# 39-996_-_SM_Clock-Timer.net
KiCad netlist of a schematic drawn in Altium Designer
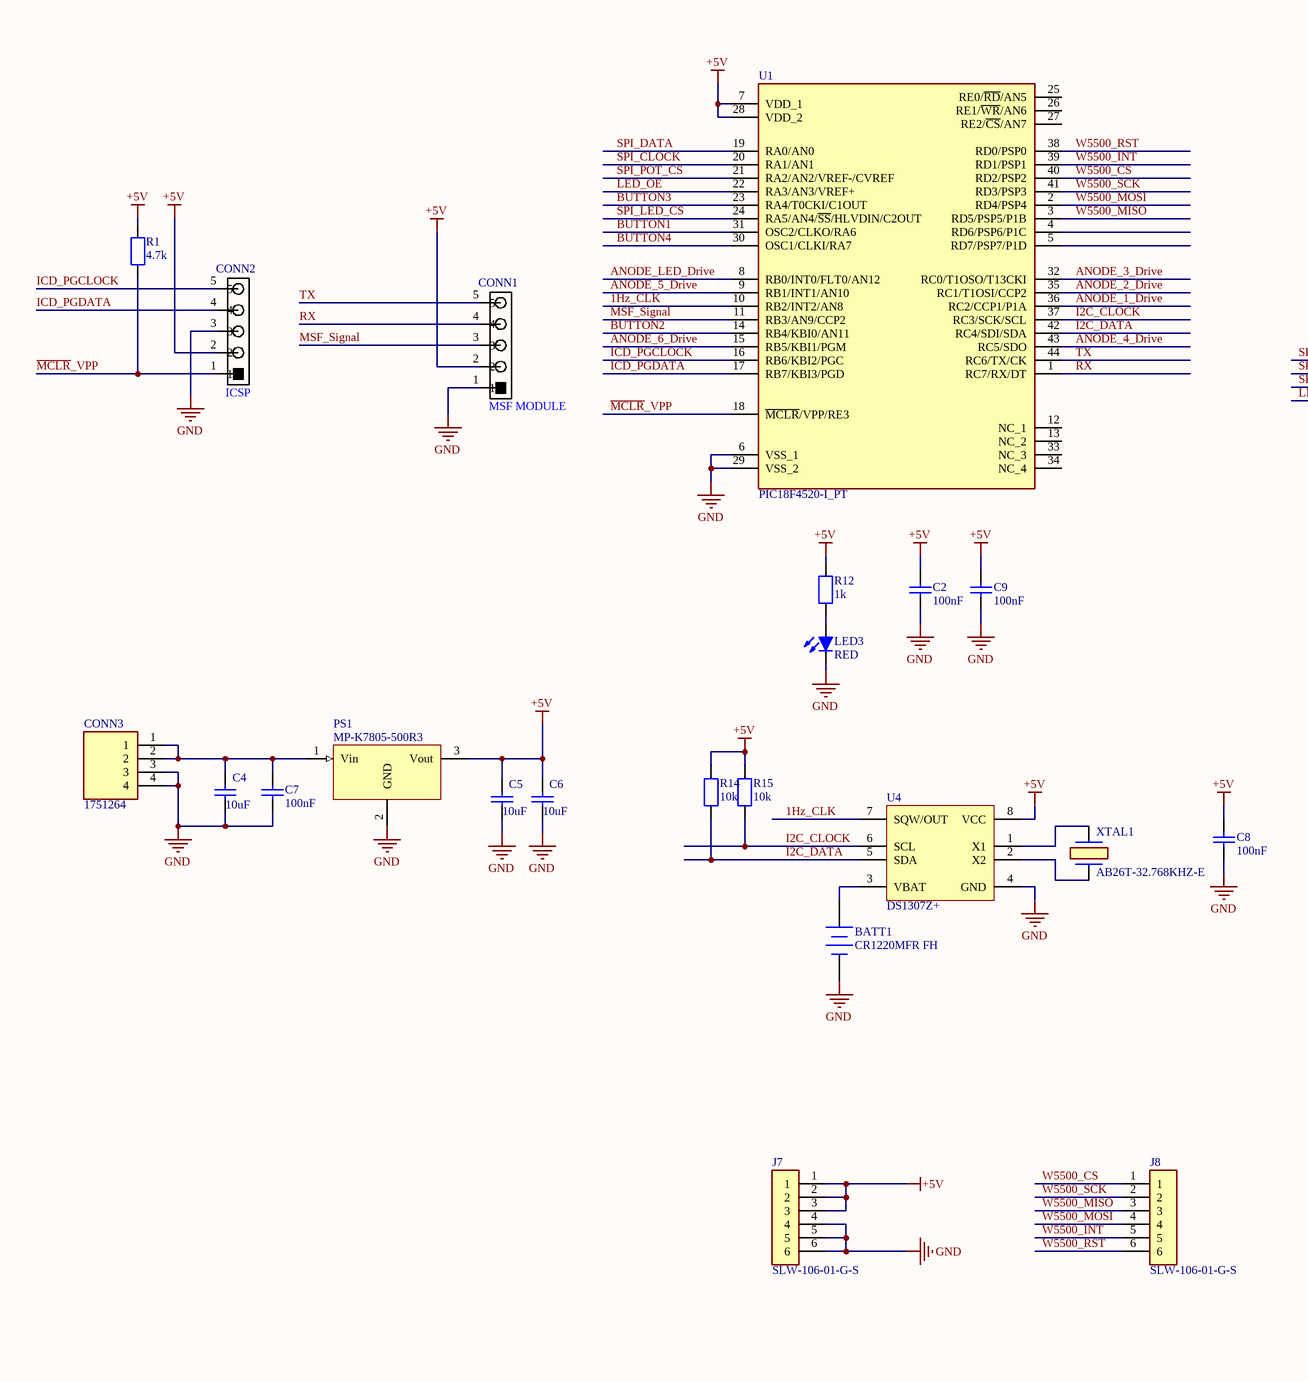
[diagram p0: 39-996 - SM Clock-Timer.SchDoc, left]
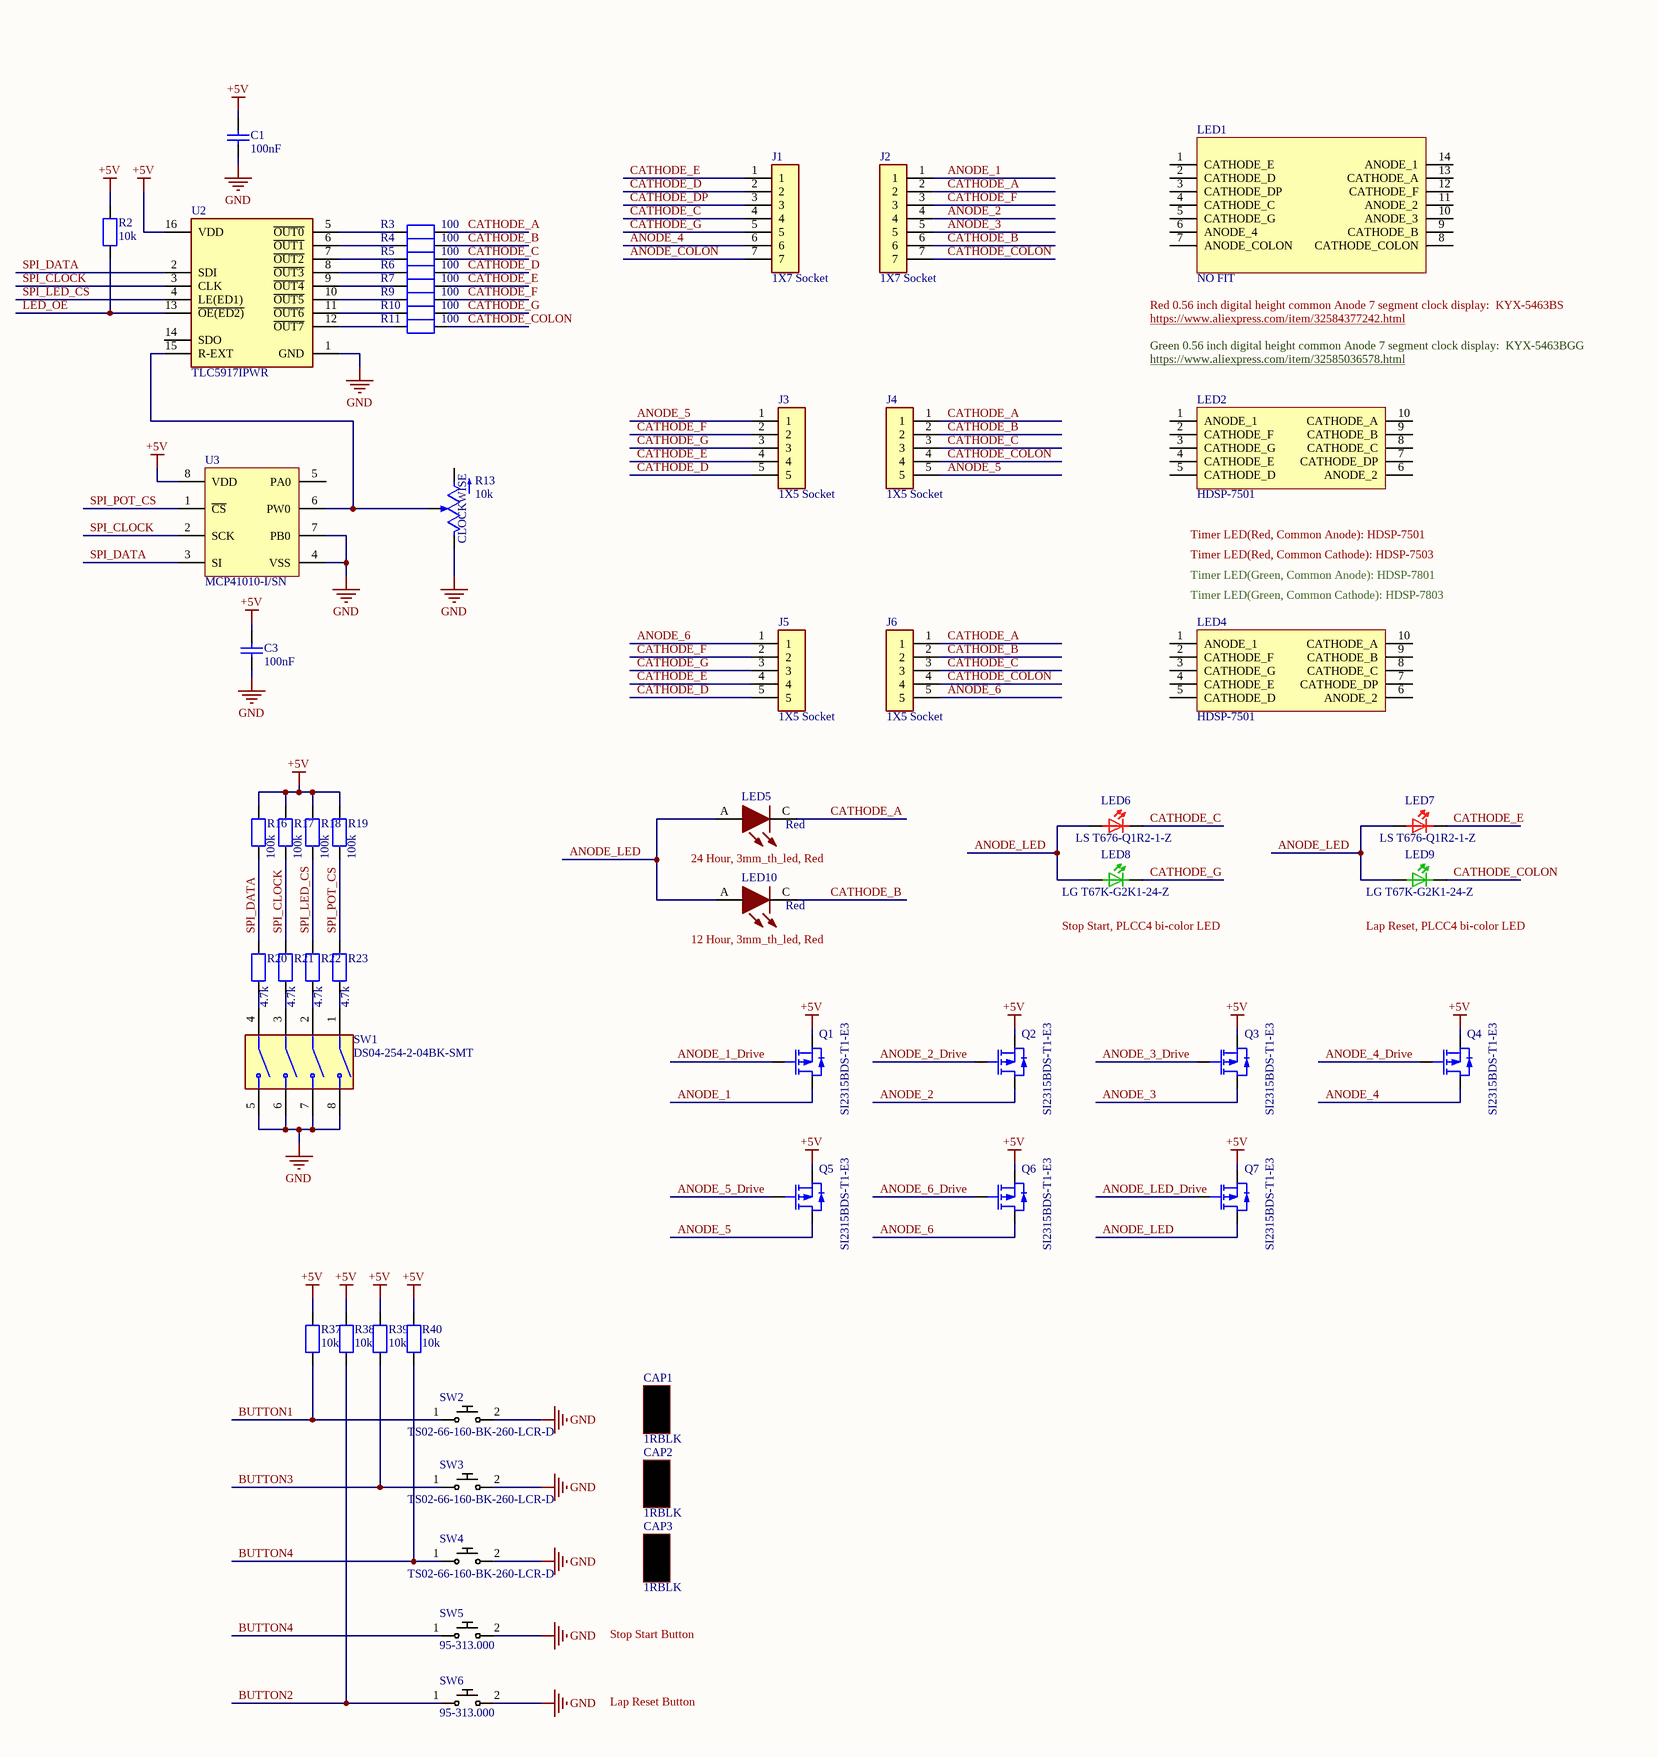
[diagram p1: 39-996 - SM Clock-Timer.SchDoc, right]

(export (version "E")
  (design (tool "Eeschema 10.0.6"))
  (components
    (comp (ref "BATT1")
      (value "CR1220MFR FH")
      (footprint "CR1220MFRFH")
      (description "Coin Cell Battery 3V2-PINHORZ40mAh")
      (fields (field (name "MANUFACTURER") "Renata"))
      (libsource (lib "SM Desk Clock-Timer") (part "CR1220MFR FH"))
    )
    (comp (ref "C1")
      (value "100nF")
      (footprint "C0603")
      (description "100nF ± 10% 50V")
      (fields (field (name "MANUFACTURER") "Yageo"))
      (libsource (lib "Cue Light Output PCB - RJ45") (part "100nF ± 10% 50V"))
    )
    (comp (ref "C2")
      (value "100nF")
      (footprint "C0603")
      (description "100nF ± 10% 50V")
      (fields (field (name "MANUFACTURER") "Yageo"))
      (libsource (lib "Cue Light Output PCB - RJ45") (part "100nF ± 10% 50V"))
    )
    (comp (ref "C3")
      (value "100nF")
      (footprint "C0603")
      (description "100nF ± 10% 50V")
      (fields (field (name "MANUFACTURER") "Yageo"))
      (libsource (lib "Cue Light Output PCB - RJ45") (part "100nF ± 10% 50V"))
    )
    (comp (ref "C4")
      (value "10uF")
      (footprint "C1206")
      (description "10uF ± 10% 50V")
      (fields (field (name "MANUFACTURER") "Yageo"))
      (libsource (lib "Cue Light Output PCB - RJ45") (part "10uF ± 10% 50V"))
    )
    (comp (ref "C5")
      (value "10uF")
      (footprint "C1206")
      (description "10uF ± 10% 50V")
      (fields (field (name "MANUFACTURER") "Yageo"))
      (libsource (lib "Cue Light Output PCB - RJ45") (part "10uF ± 10% 50V"))
    )
    (comp (ref "C6")
      (value "10uF")
      (footprint "C1206")
      (description "10uF ± 10% 50V")
      (fields (field (name "MANUFACTURER") "Yageo"))
      (libsource (lib "Cue Light Output PCB - RJ45") (part "10uF ± 10% 50V"))
    )
    (comp (ref "C7")
      (value "100nF")
      (footprint "C0603")
      (description "100nF ± 10% 50V")
      (fields (field (name "MANUFACTURER") "Yageo"))
      (libsource (lib "Cue Light Output PCB - RJ45") (part "100nF ± 10% 50V"))
    )
    (comp (ref "C8")
      (value "100nF")
      (footprint "C0603")
      (description "100nF ± 10% 50V")
      (fields (field (name "MANUFACTURER") "Yageo"))
      (libsource (lib "Cue Light Output PCB - RJ45") (part "100nF ± 10% 50V"))
    )
    (comp (ref "C9")
      (value "100nF")
      (footprint "C0603")
      (description "100nF ± 10% 50V")
      (fields (field (name "MANUFACTURER") "Yageo"))
      (libsource (lib "Cue Light Output PCB - RJ45") (part "100nF ± 10% 50V"))
    )
    (comp (ref "CAP1")
      (value "1RBLK")
      (footprint "1RBLK")
      (description "Switch Bezels / Switch Caps 9 X 5MM RND CAP BLK")
      (fields (field (name "MANUFACTURER") "E-Switch"))
      (libsource (lib "SM Desk Clock-Timer") (part "1RBLK"))
    )
    (comp (ref "CAP2")
      (value "1RBLK")
      (footprint "1RBLK")
      (description "Switch Bezels / Switch Caps 9 X 5MM RND CAP BLK")
      (fields (field (name "MANUFACTURER") "E-Switch"))
      (libsource (lib "SM Desk Clock-Timer") (part "1RBLK"))
    )
    (comp (ref "CAP3")
      (value "1RBLK")
      (footprint "1RBLK")
      (description "Switch Bezels / Switch Caps 9 X 5MM RND CAP BLK")
      (fields (field (name "MANUFACTURER") "E-Switch"))
      (libsource (lib "SM Desk Clock-Timer") (part "1RBLK"))
    )
    (comp (ref "CONN1")
      (value "NO FIT")
      (footprint "ICSP")
      (description "ICSP Header - 5 Pin, 2.54mm Pitch")
      (libsource (lib "GDS_CONN") (part "ICSP"))
    )
    (comp (ref "CONN2")
      (value "NO FIT")
      (footprint "ICSP")
      (description "ICSP Header - 5 Pin, 2.54mm Pitch")
      (libsource (lib "GDS_CONN") (part "ICSP"))
    )
    (comp (ref "CONN3")
      (value "1751264")
      (footprint "1751264")
      (description "Fixed Terminal Blocks 4P 3.5mm 90DEG")
      (fields (field (name "MANUFACTURER") "Phoenix Contact"))
      (libsource (lib "1751264") (part "1751264"))
    )
    (comp (ref "J1")
      (value "1X7 Socket")
      (footprint "D019970742")
      (description "IC & Component Sockets 7 WAY SIL VERT SKT")
      (fields (field (name "MANUFACTURER") "Harwin") (field (name "MANUFACTURER PART NUMBER") "D01-9970742"))
      (libsource (lib "SM Desk Clock-Timer") (part "D01-9970742"))
    )
    (comp (ref "J2")
      (value "1X7 Socket")
      (footprint "D019970742")
      (description "IC & Component Sockets 7 WAY SIL VERT SKT")
      (fields (field (name "MANUFACTURER") "Harwin") (field (name "MANUFACTURER PART NUMBER") "D01-9970742"))
      (libsource (lib "") (part "D01-9970742_1"))
    )
    (comp (ref "J3")
      (value "1X5 Socket")
      (footprint "D01-9970542")
      (description "IC & Component Sockets 5 WAY SIL VERT SKT")
      (fields (field (name "MANUFACTURER") "Harwin") (field (name "MANUFACTURER PART NUMBER") "D01-9970542"))
      (libsource (lib "") (part "D01-9970542_1"))
    )
    (comp (ref "J4")
      (value "1X5 Socket")
      (footprint "D01-9970542")
      (description "IC & Component Sockets 5 WAY SIL VERT SKT")
      (fields (field (name "MANUFACTURER") "Harwin") (field (name "MANUFACTURER PART NUMBER") "D01-9970542"))
      (libsource (lib "SM Desk Clock-Timer") (part "D01-9970542"))
    )
    (comp (ref "J5")
      (value "1X5 Socket")
      (footprint "D01-9970542")
      (description "IC & Component Sockets 5 WAY SIL VERT SKT")
      (fields (field (name "MANUFACTURER") "Harwin") (field (name "MANUFACTURER PART NUMBER") "D01-9970542"))
      (libsource (lib "") (part "D01-9970542_1"))
    )
    (comp (ref "J6")
      (value "1X5 Socket")
      (footprint "D01-9970542")
      (description "IC & Component Sockets 5 WAY SIL VERT SKT")
      (fields (field (name "MANUFACTURER") "Harwin") (field (name "MANUFACTURER PART NUMBER") "D01-9970542"))
      (libsource (lib "SM Desk Clock-Timer") (part "D01-9970542"))
    )
    (comp (ref "J7")
      (value "SLW-106-01-G-S")
      (footprint "SLW-106-01-G-S")
      (description "Headers & Wire Housings .100\" Tiger Buy Low Profile Socket Strip")
      (fields (field (name "MANUFACTURER") "Samtec"))
      (libsource (lib "SM Desk Clock-Timer") (part "SLW-106-01-G-S"))
    )
    (comp (ref "J8")
      (value "SLW-106-01-G-S")
      (footprint "SLW-106-01-G-S")
      (description "Headers & Wire Housings .100\" Tiger Buy Low Profile Socket Strip")
      (fields (field (name "MANUFACTURER") "Samtec"))
      (libsource (lib "") (part "SLW-106-01-G-S_1"))
    )
    (comp (ref "LED1")
      (value "NO FIT")
      (footprint "Common Cathode 7 Segment Clock Display")
      (description "0.56 inch digit height common Anode 7 segment clock display")
      (libsource (lib "SM Desk Clock-Timer") (part "Common Anode 7 Segment Clock Display"))
    )
    (comp (ref "LED2")
      (value "HDSP-7501")
      (footprint "HDSP7501")
      (description "7 SEG NUMERIC DISPLAY, HIGH EFFICIENCY RED, 7.6 mm")
      (fields (field (name "MANUFACTURER") "Avago Technologies"))
      (libsource (lib "SM Desk Clock-Timer") (part "HDSP-7501"))
    )
    (comp (ref "LED3")
      (value "RED")
      (footprint "LED_PLCC2")
      (description "Standard LEDs - SMD Super Red, 645nm 180mcd, 20mA")
      (fields
        (field (name "MANUFACTURER") "ams OSRAM")
        (field (name "MANUFACTURER PART NUMBER") "LS T676-Q1R2-1-Z")
      )
      (libsource (lib "Cue Light Output PCB - RJ45") (part "LS T676-Q1R2-1-Z"))
    )
    (comp (ref "LED4")
      (value "HDSP-7501")
      (footprint "HDSP7501")
      (description "7 SEG NUMERIC DISPLAY, HIGH EFFICIENCY RED, 7.6 mm")
      (fields (field (name "MANUFACTURER") "Avago Technologies"))
      (libsource (lib "SM Desk Clock-Timer") (part "HDSP-7501"))
    )
    (comp (ref "LED5")
      (value "Red")
      (footprint "LED_3mm")
      (description "Standard LEDs - Through Hole RED DIFFUSED")
      (fields (field (name "MANUFACTURER") "Kingbright") (field (name "MANUFACTURER PART NUMBER") "WP132XID"))
      (libsource (lib "SM Desk Clock-Timer") (part "WP132XID"))
    )
    (comp (ref "LED6")
      (value "LS T676-Q1R2-1-Z")
      (footprint "PLCC-2")
      (description "Standard LEDs - SMD Super Red, 645nm 180mcd, 20mA")
      (fields (field (name "MANUFACTURER") "ams OSRAM"))
      (libsource (lib "47-538 - Desk Power CTRL Button") (part "LS T676-Q1R2-1-Z"))
    )
    (comp (ref "LED7")
      (value "LS T676-Q1R2-1-Z")
      (footprint "PLCC-2")
      (description "Standard LEDs - SMD Super Red, 645nm 180mcd, 20mA")
      (fields (field (name "MANUFACTURER") "ams OSRAM"))
      (libsource (lib "47-538 - Desk Power CTRL Button") (part "LS T676-Q1R2-1-Z"))
    )
    (comp (ref "LED8")
      (value "LG T67K-G2K1-24-Z")
      (footprint "PLCC-2")
      (description "Standard LEDs - SMD Green 570nm, 20mA")
      (fields (field (name "MANUFACTURER") "ams OSRAM"))
      (libsource (lib "47-538 - Desk Power CTRL Button") (part "LG T67K-G2K1-24-Z"))
    )
    (comp (ref "LED9")
      (value "LG T67K-G2K1-24-Z")
      (footprint "PLCC-2")
      (description "Standard LEDs - SMD Green 570nm, 20mA")
      (fields (field (name "MANUFACTURER") "ams OSRAM"))
      (libsource (lib "47-538 - Desk Power CTRL Button") (part "LG T67K-G2K1-24-Z"))
    )
    (comp (ref "LED10")
      (value "Red")
      (footprint "LED_3mm")
      (description "Standard LEDs - Through Hole RED DIFFUSED")
      (fields (field (name "MANUFACTURER") "Kingbright") (field (name "MANUFACTURER PART NUMBER") "WP132XID"))
      (libsource (lib "SM Desk Clock-Timer") (part "WP132XID"))
    )
    (comp (ref "PS1")
      (value "MP-K7805-500R3")
      (footprint "CONV_K7805-500R3")
      (fields (field (name "MANUFACTURER") "MULTICOMP PRO"))
      (libsource (lib "SM Desk Clock-Timer") (part "MP-K7805-500R3"))
    )
    (comp (ref "Q1")
      (value "SI2315BDS-T1-E3")
      (footprint "SOT23-3")
      (description "MOSFET 1.8V 3.2A 1.25W")
      (fields (field (name "MANUFACTURER") "Vishay Semiconductors"))
      (libsource (lib "SM Desk Clock-Timer") (part "SI2315BDS-T1-E3"))
    )
    (comp (ref "Q2")
      (value "SI2315BDS-T1-E3")
      (footprint "SOT23-3")
      (description "MOSFET 1.8V 3.2A 1.25W")
      (fields (field (name "MANUFACTURER") "Vishay Semiconductors"))
      (libsource (lib "SM Desk Clock-Timer") (part "SI2315BDS-T1-E3"))
    )
    (comp (ref "Q3")
      (value "SI2315BDS-T1-E3")
      (footprint "SOT23-3")
      (description "MOSFET 1.8V 3.2A 1.25W")
      (fields (field (name "MANUFACTURER") "Vishay Semiconductors"))
      (libsource (lib "SM Desk Clock-Timer") (part "SI2315BDS-T1-E3"))
    )
    (comp (ref "Q4")
      (value "SI2315BDS-T1-E3")
      (footprint "SOT23-3")
      (description "MOSFET 1.8V 3.2A 1.25W")
      (fields (field (name "MANUFACTURER") "Vishay Semiconductors"))
      (libsource (lib "SM Desk Clock-Timer") (part "SI2315BDS-T1-E3"))
    )
    (comp (ref "Q5")
      (value "SI2315BDS-T1-E3")
      (footprint "SOT23-3")
      (description "MOSFET 1.8V 3.2A 1.25W")
      (fields (field (name "MANUFACTURER") "Vishay Semiconductors"))
      (libsource (lib "SM Desk Clock-Timer") (part "SI2315BDS-T1-E3"))
    )
    (comp (ref "Q6")
      (value "SI2315BDS-T1-E3")
      (footprint "SOT23-3")
      (description "MOSFET 1.8V 3.2A 1.25W")
      (fields (field (name "MANUFACTURER") "Vishay Semiconductors"))
      (libsource (lib "SM Desk Clock-Timer") (part "SI2315BDS-T1-E3"))
    )
    (comp (ref "Q7")
      (value "SI2315BDS-T1-E3")
      (footprint "SOT23-3")
      (description "MOSFET 1.8V 3.2A 1.25W")
      (fields (field (name "MANUFACTURER") "Vishay Semiconductors"))
      (libsource (lib "SM Desk Clock-Timer") (part "SI2315BDS-T1-E3"))
    )
    (comp (ref "R1")
      (value "4.7k")
      (footprint "R0603")
      (description "4.7 kOhms ±1% 0.1W")
      (fields
        (field (name "MANUFACTURER") "Yageo")
        (field (name "MANUFACTURER PART NUMBER") "RC0603FR-074K7L")
      )
      (libsource (lib "32-503 - DriveHUB - 1Ch 10A Variable CV") (part "4.7 kOhms ±1% 0.1W"))
    )
    (comp (ref "R2")
      (value "10k")
      (footprint "R0603")
      (description "10 kOhms ±1% 0.1W")
      (fields
        (field (name "MANUFACTURER") "Yageo")
        (field (name "MANUFACTURER PART NUMBER") "RC0603FR-0710KL")
      )
      (libsource (lib "SM Desk Clock-Timer") (part "10 kOhms ±1% 0.1W"))
    )
    (comp (ref "R3")
      (value "100")
      (footprint "R0603")
      (description "100 Ohms ±1% 0.1W")
      (fields
        (field (name "MANUFACTURER") "Yageo")
        (field (name "MANUFACTURER PART NUMBER") "RC0603FR-07100RL")
      )
      (libsource (lib "SM Desk Clock-Timer") (part "100 Ohms ±1% 0.1W"))
    )
    (comp (ref "R4")
      (value "100")
      (footprint "R0603")
      (description "100 Ohms ±1% 0.1W")
      (fields
        (field (name "MANUFACTURER") "Yageo")
        (field (name "MANUFACTURER PART NUMBER") "RC0603FR-07100RL")
      )
      (libsource (lib "SM Desk Clock-Timer") (part "100 Ohms ±1% 0.1W"))
    )
    (comp (ref "R5")
      (value "100")
      (footprint "R0603")
      (description "100 Ohms ±1% 0.1W")
      (fields
        (field (name "MANUFACTURER") "Yageo")
        (field (name "MANUFACTURER PART NUMBER") "RC0603FR-07100RL")
      )
      (libsource (lib "SM Desk Clock-Timer") (part "100 Ohms ±1% 0.1W"))
    )
    (comp (ref "R6")
      (value "100")
      (footprint "R0603")
      (description "100 Ohms ±1% 0.1W")
      (fields
        (field (name "MANUFACTURER") "Yageo")
        (field (name "MANUFACTURER PART NUMBER") "RC0603FR-07100RL")
      )
      (libsource (lib "SM Desk Clock-Timer") (part "100 Ohms ±1% 0.1W"))
    )
    (comp (ref "R7")
      (value "100")
      (footprint "R0603")
      (description "100 Ohms ±1% 0.1W")
      (fields
        (field (name "MANUFACTURER") "Yageo")
        (field (name "MANUFACTURER PART NUMBER") "RC0603FR-07100RL")
      )
      (libsource (lib "SM Desk Clock-Timer") (part "100 Ohms ±1% 0.1W"))
    )
    (comp (ref "R9")
      (value "100")
      (footprint "R0603")
      (description "100 Ohms ±1% 0.1W")
      (fields
        (field (name "MANUFACTURER") "Yageo")
        (field (name "MANUFACTURER PART NUMBER") "RC0603FR-07100RL")
      )
      (libsource (lib "SM Desk Clock-Timer") (part "100 Ohms ±1% 0.1W"))
    )
    (comp (ref "R10")
      (value "100")
      (footprint "R0603")
      (description "100 Ohms ±1% 0.1W")
      (fields
        (field (name "MANUFACTURER") "Yageo")
        (field (name "MANUFACTURER PART NUMBER") "RC0603FR-07100RL")
      )
      (libsource (lib "SM Desk Clock-Timer") (part "100 Ohms ±1% 0.1W"))
    )
    (comp (ref "R11")
      (value "100")
      (footprint "R0603")
      (description "100 Ohms ±1% 0.1W")
      (fields
        (field (name "MANUFACTURER") "Yageo")
        (field (name "MANUFACTURER PART NUMBER") "RC0603FR-07100RL")
      )
      (libsource (lib "SM Desk Clock-Timer") (part "100 Ohms ±1% 0.1W"))
    )
    (comp (ref "R12")
      (value "1k")
      (footprint "R0603")
      (description "1 kOhms ±1% 0.1W")
      (fields
        (field (name "MANUFACTURER") "Yageo")
        (field (name "MANUFACTURER PART NUMBER") "RC0603FR-071KL")
      )
      (libsource (lib "SM Desk Clock-Timer") (part "1 kOhms ±1% 0.1W"))
    )
    (comp (ref "R13")
      (value "10k")
      (footprint "TRIM_3386F-1-103LF")
      (description "Trimmer Resistors - Through Hole 3/8\" 10Kohms 10% 0.5Watts Square")
      (fields
        (field (name "MANUFACTURER") "Bourns")
        (field (name "MANUFACTURER PART NUMBER") "3386F-1-103LF")
      )
      (libsource (lib "SM Desk Clock-Timer") (part "3386F-1-103LF"))
    )
    (comp (ref "R14")
      (value "10k")
      (footprint "R0603")
      (description "10 kOhms ±1% 0.1W")
      (fields
        (field (name "MANUFACTURER") "Yageo")
        (field (name "MANUFACTURER PART NUMBER") "RC0603FR-0710KL")
      )
      (libsource (lib "SM Desk Clock-Timer") (part "10 kOhms ±1% 0.1W"))
    )
    (comp (ref "R15")
      (value "10k")
      (footprint "R0603")
      (description "10 kOhms ±1% 0.1W")
      (fields
        (field (name "MANUFACTURER") "Yageo")
        (field (name "MANUFACTURER PART NUMBER") "RC0603FR-0710KL")
      )
      (libsource (lib "SM Desk Clock-Timer") (part "10 kOhms ±1% 0.1W"))
    )
    (comp (ref "R16")
      (value "100k")
      (footprint "R0603")
      (description "100 kOhms ±1% 0.1W")
      (fields
        (field (name "MANUFACTURER") "Yageo")
        (field (name "MANUFACTURER PART NUMBER") "RC0603FR-07100KL")
      )
      (libsource (lib "SM Desk Clock-Timer") (part "100 kOhms ±1% 0.1W"))
    )
    (comp (ref "R17")
      (value "100k")
      (footprint "R0603")
      (description "100 kOhms ±1% 0.1W")
      (fields
        (field (name "MANUFACTURER") "Yageo")
        (field (name "MANUFACTURER PART NUMBER") "RC0603FR-07100KL")
      )
      (libsource (lib "SM Desk Clock-Timer") (part "100 kOhms ±1% 0.1W"))
    )
    (comp (ref "R18")
      (value "100k")
      (footprint "R0603")
      (description "100 kOhms ±1% 0.1W")
      (fields
        (field (name "MANUFACTURER") "Yageo")
        (field (name "MANUFACTURER PART NUMBER") "RC0603FR-07100KL")
      )
      (libsource (lib "SM Desk Clock-Timer") (part "100 kOhms ±1% 0.1W"))
    )
    (comp (ref "R19")
      (value "100k")
      (footprint "R0603")
      (description "100 kOhms ±1% 0.1W")
      (fields
        (field (name "MANUFACTURER") "Yageo")
        (field (name "MANUFACTURER PART NUMBER") "RC0603FR-07100KL")
      )
      (libsource (lib "SM Desk Clock-Timer") (part "100 kOhms ±1% 0.1W"))
    )
    (comp (ref "R20")
      (value "4.7k")
      (footprint "R0603")
      (description "4.7 kOhms ±1% 0.1W")
      (fields
        (field (name "MANUFACTURER") "Yageo")
        (field (name "MANUFACTURER PART NUMBER") "RC0603FR-074K7L")
      )
      (libsource (lib "32-503 - DriveHUB - 1Ch 10A Variable CV") (part "4.7 kOhms ±1% 0.1W"))
    )
    (comp (ref "R21")
      (value "4.7k")
      (footprint "R0603")
      (description "4.7 kOhms ±1% 0.1W")
      (fields
        (field (name "MANUFACTURER") "Yageo")
        (field (name "MANUFACTURER PART NUMBER") "RC0603FR-074K7L")
      )
      (libsource (lib "32-503 - DriveHUB - 1Ch 10A Variable CV") (part "4.7 kOhms ±1% 0.1W"))
    )
    (comp (ref "R22")
      (value "4.7k")
      (footprint "R0603")
      (description "4.7 kOhms ±1% 0.1W")
      (fields
        (field (name "MANUFACTURER") "Yageo")
        (field (name "MANUFACTURER PART NUMBER") "RC0603FR-074K7L")
      )
      (libsource (lib "32-503 - DriveHUB - 1Ch 10A Variable CV") (part "4.7 kOhms ±1% 0.1W"))
    )
    (comp (ref "R23")
      (value "4.7k")
      (footprint "R0603")
      (description "4.7 kOhms ±1% 0.1W")
      (fields
        (field (name "MANUFACTURER") "Yageo")
        (field (name "MANUFACTURER PART NUMBER") "RC0603FR-074K7L")
      )
      (libsource (lib "32-503 - DriveHUB - 1Ch 10A Variable CV") (part "4.7 kOhms ±1% 0.1W"))
    )
    (comp (ref "R37")
      (value "10k")
      (footprint "R0603")
      (description "10 kOhms ±1% 0.1W")
      (fields
        (field (name "MANUFACTURER") "Yageo")
        (field (name "MANUFACTURER PART NUMBER") "RC0603FR-0710KL")
      )
      (libsource (lib "SM Desk Clock-Timer") (part "10 kOhms ±1% 0.1W"))
    )
    (comp (ref "R38")
      (value "10k")
      (footprint "R0603")
      (description "10 kOhms ±1% 0.1W")
      (fields
        (field (name "MANUFACTURER") "Yageo")
        (field (name "MANUFACTURER PART NUMBER") "RC0603FR-0710KL")
      )
      (libsource (lib "SM Desk Clock-Timer") (part "10 kOhms ±1% 0.1W"))
    )
    (comp (ref "R39")
      (value "10k")
      (footprint "R0603")
      (description "10 kOhms ±1% 0.1W")
      (fields
        (field (name "MANUFACTURER") "Yageo")
        (field (name "MANUFACTURER PART NUMBER") "RC0603FR-0710KL")
      )
      (libsource (lib "SM Desk Clock-Timer") (part "10 kOhms ±1% 0.1W"))
    )
    (comp (ref "R40")
      (value "10k")
      (footprint "R0603")
      (description "10 kOhms ±1% 0.1W")
      (fields
        (field (name "MANUFACTURER") "Yageo")
        (field (name "MANUFACTURER PART NUMBER") "RC0603FR-0710KL")
      )
      (libsource (lib "SM Desk Clock-Timer") (part "10 kOhms ±1% 0.1W"))
    )
    (comp (ref "SW1")
      (value "DS04-254-2-04BK-SMT")
      (footprint "SW_DS04-254-2-04BK-SMT")
      (description "DIP Switches/SIP Switches DIP Switch, SPST, 2.54 pitch, flat actuator, SMT, 4 position, Black")
      (fields (field (name "MANUFACTURER") "CUI Devices"))
      (libsource (lib "SM Desk Clock-Timer") (part "DS04-254-2-04BK-SMT"))
    )
    (comp (ref "SW2")
      (value "TS02-66-160-BK-260-LCR-D")
      (footprint "SW_TS02-66-160-BK-260-LCR-D")
      (description "Tactile Switches 6 x 6 mm, 16 mm Act Height, 260 gf, Black, Long Crimped, Through Hole, SPST,")
      (fields (field (name "MANUFACTURER") "CUI Devices"))
      (libsource (lib "SM Desk Clock-Timer") (part "TS02-66-160-BK-260-LCR-D"))
    )
    (comp (ref "SW3")
      (value "TS02-66-160-BK-260-LCR-D")
      (footprint "SW_TS02-66-160-BK-260-LCR-D")
      (description "Tactile Switches 6 x 6 mm, 16 mm Act Height, 260 gf, Black, Long Crimped, Through Hole, SPST,")
      (fields (field (name "MANUFACTURER") "CUI Devices"))
      (libsource (lib "SM Desk Clock-Timer") (part "TS02-66-160-BK-260-LCR-D"))
    )
    (comp (ref "SW4")
      (value "TS02-66-160-BK-260-LCR-D")
      (footprint "SW_TS02-66-160-BK-260-LCR-D")
      (description "Tactile Switches 6 x 6 mm, 16 mm Act Height, 260 gf, Black, Long Crimped, Through Hole, SPST,")
      (fields (field (name "MANUFACTURER") "CUI Devices"))
      (libsource (lib "SM Desk Clock-Timer") (part "TS02-66-160-BK-260-LCR-D"))
    )
    (comp (ref "SW5")
      (value "95-313.000")
      (footprint "PUSHBUTTON_95-313.000")
      (description "Switching element square, 12.7 x 12.7 mm")
      (fields (field (name "MANUFACTURER") "eao"))
      (libsource (lib "47-538 - Desk Power CTRL Button") (part "95-313.000"))
    )
    (comp (ref "SW6")
      (value "95-313.000")
      (footprint "PUSHBUTTON_95-313.000")
      (description "Switching element square, 12.7 x 12.7 mm")
      (fields (field (name "MANUFACTURER") "eao"))
      (libsource (lib "47-538 - Desk Power CTRL Button") (part "95-313.000"))
    )
    (comp (ref "U1")
      (value "PIC18F4520-I_PT")
      (footprint "TQFP-44")
      (description "MCU 32 KB Flash,1536 RAM, 36 I/O")
      (fields
        (field (name "MANUFACTURER") "Microchip")
        (field (name "MANUFACTURER PART NUMBER") "PIC18F4520-I/PT")
      )
      (libsource (lib "SM Desk Clock-Timer") (part "PIC18F4520-I_PT"))
    )
    (comp (ref "U2")
      (value "TLC5917IPWR")
      (footprint "SOIC-16")
      (description "LED Lighting Drivers 8B Constant-Current LED Sink")
      (fields (field (name "MANUFACTURER") "Texas Instruments"))
      (libsource (lib "SM Desk Clock-Timer") (part "TLC5917IPWR"))
    )
    (comp (ref "U3")
      (value "MCP41010-I/SN")
      (footprint "SOIC-8")
      (description "Digital Potentiometer 10K 256pos SPI SO8")
      (fields (field (name "MANUFACTURER") "Microchip"))
      (libsource (lib "SM Desk Clock-Timer") (part "MCP41010-I/SN"))
    )
    (comp (ref "U4")
      (value "DS1307Z+")
      (footprint "SOIC-8")
      (description "DS1307Z+, Real Time Clock, Alarm, Calendar, Clock, 56B RAM, I2C, 5V, 8-Pin SOIC")
      (fields (field (name "MANUFACTURER") "Analog Devices"))
      (libsource (lib "SM Desk Clock-Timer") (part "DS1307Z+"))
    )
    (comp (ref "XTAL1")
      (value "AB26T-32.768KHZ-E")
      (footprint "AB26T32768KHZE")
      (description "OSC XO 1.33GHZ 2.5V LVPECL")
      (fields (field (name "MANUFACTURER") "ABRACON"))
      (libsource (lib "SM Desk Clock-Timer") (part "AB26T-32.768KHZ-E"))
    )
  )
  (nets
    (net (code "1") (name "+5V") (class "Default")
      (node (ref "C1") (pin "2") (pinfunction "2_2") (pintype "passive"))
      (node (ref "C2") (pin "2") (pinfunction "2_2") (pintype "passive"))
      (node (ref "C3") (pin "2") (pinfunction "2_2") (pintype "passive"))
      (node (ref "C5") (pin "2") (pinfunction "2_2") (pintype "passive"))
      (node (ref "C6") (pin "2") (pinfunction "2_2") (pintype "passive"))
      (node (ref "C8") (pin "2") (pinfunction "2_2") (pintype "passive"))
      (node (ref "C9") (pin "2") (pinfunction "2_2") (pintype "passive"))
      (node (ref "CONN1") (pin "2") (pinfunction "2_2") (pintype "passive"))
      (node (ref "CONN2") (pin "2") (pinfunction "2_2") (pintype "passive"))
      (node (ref "J7") (pin "1") (pinfunction "1_1") (pintype "passive"))
      (node (ref "J7") (pin "2") (pinfunction "2_2") (pintype "passive"))
      (node (ref "J7") (pin "3") (pinfunction "3_3") (pintype "passive"))
      (node (ref "PS1") (pin "3") (pinfunction "Vout_3") (pintype "passive"))
      (node (ref "Q1") (pin "2") (pinfunction "S_2") (pintype "passive"))
      (node (ref "Q2") (pin "2") (pinfunction "S_2") (pintype "passive"))
      (node (ref "Q3") (pin "2") (pinfunction "S_2") (pintype "passive"))
      (node (ref "Q4") (pin "2") (pinfunction "S_2") (pintype "passive"))
      (node (ref "Q5") (pin "2") (pinfunction "S_2") (pintype "passive"))
      (node (ref "Q6") (pin "2") (pinfunction "S_2") (pintype "passive"))
      (node (ref "Q7") (pin "2") (pinfunction "S_2") (pintype "passive"))
      (node (ref "R1") (pin "2") (pinfunction "2_2") (pintype "passive"))
      (node (ref "R12") (pin "2") (pinfunction "2_2") (pintype "passive"))
      (node (ref "R14") (pin "2") (pinfunction "2_2") (pintype "passive"))
      (node (ref "R15") (pin "2") (pinfunction "2_2") (pintype "passive"))
      (node (ref "R16") (pin "2") (pinfunction "2_2") (pintype "passive"))
      (node (ref "R17") (pin "2") (pinfunction "2_2") (pintype "passive"))
      (node (ref "R18") (pin "2") (pinfunction "2_2") (pintype "passive"))
      (node (ref "R19") (pin "2") (pinfunction "2_2") (pintype "passive"))
      (node (ref "R2") (pin "2") (pinfunction "2_2") (pintype "passive"))
      (node (ref "R37") (pin "2") (pinfunction "2_2") (pintype "passive"))
      (node (ref "R38") (pin "2") (pinfunction "2_2") (pintype "passive"))
      (node (ref "R39") (pin "2") (pinfunction "2_2") (pintype "passive"))
      (node (ref "R40") (pin "2") (pinfunction "2_2") (pintype "passive"))
      (node (ref "U1") (pin "28") (pinfunction "VDD_2_28") (pintype "passive"))
      (node (ref "U1") (pin "7") (pinfunction "VDD_1_7") (pintype "passive"))
      (node (ref "U2") (pin "16") (pinfunction "VDD_16") (pintype "passive"))
      (node (ref "U3") (pin "8") (pinfunction "VDD_8") (pintype "passive"))
      (node (ref "U4") (pin "8") (pinfunction "VCC_8") (pintype "passive"))
    )
    (net (code "2") (name "/1Hz_CLK") (class "Default")
      (node (ref "U1") (pin "10") (pinfunction "RB2/INT2/AN8_10") (pintype "passive"))
      (node (ref "U4") (pin "7") (pinfunction "SQW/OUT_7") (pintype "passive"))
    )
    (net (code "3") (name "/ANODE_1") (class "Default")
      (node (ref "J2") (pin "1") (pinfunction "1_1") (pintype "passive"))
      (node (ref "Q1") (pin "3") (pinfunction "D_3") (pintype "passive"))
    )
    (net (code "4") (name "/ANODE_1_Drive") (class "Default")
      (node (ref "Q1") (pin "1") (pinfunction "G_1") (pintype "passive"))
      (node (ref "U1") (pin "36") (pinfunction "RC2/CCP1/P1A_36") (pintype "passive"))
    )
    (net (code "5") (name "/ANODE_2") (class "Default")
      (node (ref "J2") (pin "4") (pinfunction "4_4") (pintype "passive"))
      (node (ref "Q2") (pin "3") (pinfunction "D_3") (pintype "passive"))
    )
    (net (code "6") (name "/ANODE_2_Drive") (class "Default")
      (node (ref "Q2") (pin "1") (pinfunction "G_1") (pintype "passive"))
      (node (ref "U1") (pin "35") (pinfunction "RC1/T1OSI/CCP2_35") (pintype "passive"))
    )
    (net (code "7") (name "/ANODE_3") (class "Default")
      (node (ref "J2") (pin "5") (pinfunction "5_5") (pintype "passive"))
      (node (ref "Q3") (pin "3") (pinfunction "D_3") (pintype "passive"))
    )
    (net (code "8") (name "/ANODE_3_Drive") (class "Default")
      (node (ref "Q3") (pin "1") (pinfunction "G_1") (pintype "passive"))
      (node (ref "U1") (pin "32") (pinfunction "RC0/T1OSO/T13CKI_32") (pintype "passive"))
    )
    (net (code "9") (name "/ANODE_4") (class "Default")
      (node (ref "J1") (pin "6") (pinfunction "6_6") (pintype "passive"))
      (node (ref "Q4") (pin "3") (pinfunction "D_3") (pintype "passive"))
    )
    (net (code "10") (name "/ANODE_4_Drive") (class "Default")
      (node (ref "Q4") (pin "1") (pinfunction "G_1") (pintype "passive"))
      (node (ref "U1") (pin "43") (pinfunction "RC5/SDO_43") (pintype "passive"))
    )
    (net (code "11") (name "/ANODE_5") (class "Default")
      (node (ref "J3") (pin "1") (pinfunction "1_1") (pintype "passive"))
      (node (ref "J4") (pin "5") (pinfunction "5_5") (pintype "passive"))
      (node (ref "Q5") (pin "3") (pinfunction "D_3") (pintype "passive"))
    )
    (net (code "12") (name "/ANODE_5_Drive") (class "Default")
      (node (ref "Q5") (pin "1") (pinfunction "G_1") (pintype "passive"))
      (node (ref "U1") (pin "9") (pinfunction "RB1/INT1/AN10_9") (pintype "passive"))
    )
    (net (code "13") (name "/ANODE_6") (class "Default")
      (node (ref "J5") (pin "1") (pinfunction "1_1") (pintype "passive"))
      (node (ref "J6") (pin "5") (pinfunction "5_5") (pintype "passive"))
      (node (ref "Q6") (pin "3") (pinfunction "D_3") (pintype "passive"))
    )
    (net (code "14") (name "/ANODE_6_Drive") (class "Default")
      (node (ref "Q6") (pin "1") (pinfunction "G_1") (pintype "passive"))
      (node (ref "U1") (pin "15") (pinfunction "RB5/KBI1/PGM_15") (pintype "passive"))
    )
    (net (code "15") (name "/ANODE_COLON") (class "Default")
      (node (ref "J1") (pin "7") (pinfunction "7_7") (pintype "passive"))
    )
    (net (code "16") (name "/ANODE_LED") (class "Default")
      (node (ref "LED10") (pin "A") (pinfunction "A_A") (pintype "passive"))
      (node (ref "LED5") (pin "A") (pinfunction "A_A") (pintype "passive"))
      (node (ref "LED6") (pin "A") (pinfunction "A_A") (pintype "passive"))
      (node (ref "LED7") (pin "A") (pinfunction "A_A") (pintype "passive"))
      (node (ref "LED8") (pin "A") (pinfunction "A_A") (pintype "passive"))
      (node (ref "LED9") (pin "A") (pinfunction "A_A") (pintype "passive"))
      (node (ref "Q7") (pin "3") (pinfunction "D_3") (pintype "passive"))
    )
    (net (code "17") (name "/ANODE_LED_Drive") (class "Default")
      (node (ref "Q7") (pin "1") (pinfunction "G_1") (pintype "passive"))
      (node (ref "U1") (pin "8") (pinfunction "RB0/INT0/FLT0/AN12_8") (pintype "passive"))
    )
    (net (code "18") (name "/BUTTON1") (class "Default")
      (node (ref "R37") (pin "1") (pinfunction "1_1") (pintype "passive"))
      (node (ref "SW2") (pin "1") (pinfunction "1_1") (pintype "passive"))
      (node (ref "U1") (pin "31") (pinfunction "OSC2/CLKO/RA6_31") (pintype "passive"))
    )
    (net (code "19") (name "/BUTTON2") (class "Default")
      (node (ref "R38") (pin "1") (pinfunction "1_1") (pintype "passive"))
      (node (ref "SW6") (pin "1") (pinfunction "1_1") (pintype "passive"))
      (node (ref "U1") (pin "14") (pinfunction "RB4/KBI0/AN11_14") (pintype "passive"))
    )
    (net (code "20") (name "/BUTTON3") (class "Default")
      (node (ref "R39") (pin "1") (pinfunction "1_1") (pintype "passive"))
      (node (ref "SW3") (pin "1") (pinfunction "1_1") (pintype "passive"))
      (node (ref "U1") (pin "23") (pinfunction "RA4/T0CKI/C1OUT_23") (pintype "passive"))
    )
    (net (code "21") (name "/BUTTON4") (class "Default")
      (node (ref "R40") (pin "1") (pinfunction "1_1") (pintype "passive"))
      (node (ref "SW4") (pin "1") (pinfunction "1_1") (pintype "passive"))
      (node (ref "SW5") (pin "1") (pinfunction "1_1") (pintype "passive"))
      (node (ref "U1") (pin "30") (pinfunction "OSC1/CLKI/RA7_30") (pintype "passive"))
    )
    (net (code "22") (name "/CATHODE_A") (class "Default")
      (node (ref "J2") (pin "2") (pinfunction "2_2") (pintype "passive"))
      (node (ref "J4") (pin "1") (pinfunction "1_1") (pintype "passive"))
      (node (ref "J6") (pin "1") (pinfunction "1_1") (pintype "passive"))
      (node (ref "LED5") (pin "C") (pinfunction "C_C") (pintype "passive"))
      (node (ref "R3") (pin "2") (pinfunction "2_2") (pintype "passive"))
    )
    (net (code "23") (name "/CATHODE_B") (class "Default")
      (node (ref "J2") (pin "6") (pinfunction "6_6") (pintype "passive"))
      (node (ref "J4") (pin "2") (pinfunction "2_2") (pintype "passive"))
      (node (ref "J6") (pin "2") (pinfunction "2_2") (pintype "passive"))
      (node (ref "LED10") (pin "C") (pinfunction "C_C") (pintype "passive"))
      (node (ref "R4") (pin "2") (pinfunction "2_2") (pintype "passive"))
    )
    (net (code "24") (name "/CATHODE_C") (class "Default")
      (node (ref "J1") (pin "4") (pinfunction "4_4") (pintype "passive"))
      (node (ref "J4") (pin "3") (pinfunction "3_3") (pintype "passive"))
      (node (ref "J6") (pin "3") (pinfunction "3_3") (pintype "passive"))
      (node (ref "LED6") (pin "C") (pinfunction "C_C") (pintype "passive"))
      (node (ref "R5") (pin "2") (pinfunction "2_2") (pintype "passive"))
    )
    (net (code "25") (name "/CATHODE_COLON") (class "Default")
      (node (ref "J2") (pin "7") (pinfunction "7_7") (pintype "passive"))
      (node (ref "J4") (pin "4") (pinfunction "4_4") (pintype "passive"))
      (node (ref "J6") (pin "4") (pinfunction "4_4") (pintype "passive"))
      (node (ref "LED9") (pin "C") (pinfunction "C_C") (pintype "passive"))
      (node (ref "R11") (pin "2") (pinfunction "2_2") (pintype "passive"))
    )
    (net (code "26") (name "/CATHODE_D") (class "Default")
      (node (ref "J1") (pin "2") (pinfunction "2_2") (pintype "passive"))
      (node (ref "J3") (pin "5") (pinfunction "5_5") (pintype "passive"))
      (node (ref "J5") (pin "5") (pinfunction "5_5") (pintype "passive"))
      (node (ref "R6") (pin "2") (pinfunction "2_2") (pintype "passive"))
    )
    (net (code "27") (name "/CATHODE_DP") (class "Default")
      (node (ref "J1") (pin "3") (pinfunction "3_3") (pintype "passive"))
    )
    (net (code "28") (name "/CATHODE_E") (class "Default")
      (node (ref "J1") (pin "1") (pinfunction "1_1") (pintype "passive"))
      (node (ref "J3") (pin "4") (pinfunction "4_4") (pintype "passive"))
      (node (ref "J5") (pin "4") (pinfunction "4_4") (pintype "passive"))
      (node (ref "LED7") (pin "C") (pinfunction "C_C") (pintype "passive"))
      (node (ref "R7") (pin "2") (pinfunction "2_2") (pintype "passive"))
    )
    (net (code "29") (name "/CATHODE_F") (class "Default")
      (node (ref "J2") (pin "3") (pinfunction "3_3") (pintype "passive"))
      (node (ref "J3") (pin "2") (pinfunction "2_2") (pintype "passive"))
      (node (ref "J5") (pin "2") (pinfunction "2_2") (pintype "passive"))
      (node (ref "R9") (pin "2") (pinfunction "2_2") (pintype "passive"))
    )
    (net (code "30") (name "/CATHODE_G") (class "Default")
      (node (ref "J1") (pin "5") (pinfunction "5_5") (pintype "passive"))
      (node (ref "J3") (pin "3") (pinfunction "3_3") (pintype "passive"))
      (node (ref "J5") (pin "3") (pinfunction "3_3") (pintype "passive"))
      (node (ref "LED8") (pin "C") (pinfunction "C_C") (pintype "passive"))
      (node (ref "R10") (pin "2") (pinfunction "2_2") (pintype "passive"))
    )
    (net (code "31") (name "/I2C_CLOCK") (class "Default")
      (node (ref "R15") (pin "1") (pinfunction "1_1") (pintype "passive"))
      (node (ref "U1") (pin "37") (pinfunction "RC3/SCK/SCL_37") (pintype "passive"))
      (node (ref "U4") (pin "6") (pinfunction "SCL_6") (pintype "passive"))
    )
    (net (code "32") (name "/I2C_DATA") (class "Default")
      (node (ref "R14") (pin "1") (pinfunction "1_1") (pintype "passive"))
      (node (ref "U1") (pin "42") (pinfunction "RC4/SDI/SDA_42") (pintype "passive"))
      (node (ref "U4") (pin "5") (pinfunction "SDA_5") (pintype "passive"))
    )
    (net (code "33") (name "/ICD_PGCLOCK") (class "Default")
      (node (ref "CONN2") (pin "5") (pinfunction "5_5") (pintype "passive"))
      (node (ref "U1") (pin "16") (pinfunction "RB6/KBI2/PGC_16") (pintype "passive"))
    )
    (net (code "34") (name "/ICD_PGDATA") (class "Default")
      (node (ref "CONN2") (pin "4") (pinfunction "4_4") (pintype "passive"))
      (node (ref "U1") (pin "17") (pinfunction "RB7/KBI3/PGD_17") (pintype "passive"))
    )
    (net (code "35") (name "/MSF_Signal") (class "Default")
      (node (ref "CONN1") (pin "3") (pinfunction "3_3") (pintype "passive"))
      (node (ref "U1") (pin "11") (pinfunction "RB3/AN9/CCP2_11") (pintype "passive"))
    )
    (net (code "36") (name "/RX") (class "Default")
      (node (ref "CONN1") (pin "4") (pinfunction "4_4") (pintype "passive"))
      (node (ref "U1") (pin "1") (pinfunction "RC7/RX/DT_1") (pintype "passive"))
    )
    (net (code "37") (name "/SPI_CLOCK") (class "Default")
      (node (ref "R17") (pin "1") (pinfunction "1_1") (pintype "passive"))
      (node (ref "R21") (pin "2") (pinfunction "2_2") (pintype "passive"))
      (node (ref "U1") (pin "20") (pinfunction "RA1/AN1_20") (pintype "passive"))
      (node (ref "U2") (pin "3") (pinfunction "CLK_3") (pintype "passive"))
      (node (ref "U3") (pin "2") (pinfunction "SCK_2") (pintype "passive"))
    )
    (net (code "38") (name "/SPI_DATA") (class "Default")
      (node (ref "R16") (pin "1") (pinfunction "1_1") (pintype "passive"))
      (node (ref "R20") (pin "2") (pinfunction "2_2") (pintype "passive"))
      (node (ref "U1") (pin "19") (pinfunction "RA0/AN0_19") (pintype "passive"))
      (node (ref "U2") (pin "2") (pinfunction "SDI_2") (pintype "passive"))
      (node (ref "U3") (pin "3") (pinfunction "SI_3") (pintype "passive"))
    )
    (net (code "39") (name "/SPI_LED_CS") (class "Default")
      (node (ref "R18") (pin "1") (pinfunction "1_1") (pintype "passive"))
      (node (ref "R22") (pin "2") (pinfunction "2_2") (pintype "passive"))
      (node (ref "U1") (pin "24") (pinfunction "RA5/AN4/~{SS}/HLVDIN/C2OUT_24") (pintype "passive"))
      (node (ref "U2") (pin "4") (pinfunction "LE(ED1)_4") (pintype "passive"))
    )
    (net (code "40") (name "/SPI_POT_CS") (class "Default")
      (node (ref "R19") (pin "1") (pinfunction "1_1") (pintype "passive"))
      (node (ref "R23") (pin "2") (pinfunction "2_2") (pintype "passive"))
      (node (ref "U1") (pin "21") (pinfunction "RA2/AN2/VREF-/CVREF_21") (pintype "passive"))
      (node (ref "U3") (pin "1") (pinfunction "~{CS}_1") (pintype "passive"))
    )
    (net (code "41") (name "/TX") (class "Default")
      (node (ref "CONN1") (pin "5") (pinfunction "5_5") (pintype "passive"))
      (node (ref "U1") (pin "44") (pinfunction "RC6/TX/CK_44") (pintype "passive"))
    )
    (net (code "42") (name "/W5500_CS") (class "Default")
      (node (ref "J8") (pin "1") (pinfunction "1_1") (pintype "passive"))
      (node (ref "U1") (pin "40") (pinfunction "RD2/PSP2_40") (pintype "passive"))
    )
    (net (code "43") (name "/W5500_INT") (class "Default")
      (node (ref "J8") (pin "5") (pinfunction "5_5") (pintype "passive"))
      (node (ref "U1") (pin "39") (pinfunction "RD1/PSP1_39") (pintype "passive"))
    )
    (net (code "44") (name "/W5500_MISO") (class "Default")
      (node (ref "J8") (pin "3") (pinfunction "3_3") (pintype "passive"))
      (node (ref "U1") (pin "3") (pinfunction "RD5/PSP5/P1B_3") (pintype "passive"))
    )
    (net (code "45") (name "/W5500_MOSI") (class "Default")
      (node (ref "J8") (pin "4") (pinfunction "4_4") (pintype "passive"))
      (node (ref "U1") (pin "2") (pinfunction "RD4/PSP4_2") (pintype "passive"))
    )
    (net (code "46") (name "/W5500_RST") (class "Default")
      (node (ref "J8") (pin "6") (pinfunction "6_6") (pintype "passive"))
      (node (ref "U1") (pin "38") (pinfunction "RD0/PSP0_38") (pintype "passive"))
    )
    (net (code "47") (name "/W5500_SCK") (class "Default")
      (node (ref "J8") (pin "2") (pinfunction "2_2") (pintype "passive"))
      (node (ref "U1") (pin "41") (pinfunction "RD3/PSP3_41") (pintype "passive"))
    )
    (net (code "48") (name "/~{LED_OE}") (class "Default")
      (node (ref "R2") (pin "1") (pinfunction "1_1") (pintype "passive"))
      (node (ref "U1") (pin "22") (pinfunction "RA3/AN3/VREF+_22") (pintype "passive"))
      (node (ref "U2") (pin "13") (pinfunction "~{OE(ED2)}_13") (pintype "passive"))
    )
    (net (code "49") (name "/~{MCLR}_VPP") (class "Default")
      (node (ref "CONN2") (pin "1") (pinfunction "1_1") (pintype "passive"))
      (node (ref "R1") (pin "1") (pinfunction "1_1") (pintype "passive"))
      (node (ref "U1") (pin "18") (pinfunction "~{MCLR}/VPP/RE3_18") (pintype "passive"))
    )
    (net (code "50") (name "GND") (class "Default")
      (node (ref "BATT1") (pin "-") (pinfunction "-_-") (pintype "passive"))
      (node (ref "C1") (pin "1") (pinfunction "1_1") (pintype "passive"))
      (node (ref "C2") (pin "1") (pinfunction "1_1") (pintype "passive"))
      (node (ref "C3") (pin "1") (pinfunction "1_1") (pintype "passive"))
      (node (ref "C4") (pin "1") (pinfunction "1_1") (pintype "passive"))
      (node (ref "C5") (pin "1") (pinfunction "1_1") (pintype "passive"))
      (node (ref "C6") (pin "1") (pinfunction "1_1") (pintype "passive"))
      (node (ref "C7") (pin "1") (pinfunction "1_1") (pintype "passive"))
      (node (ref "C8") (pin "1") (pinfunction "1_1") (pintype "passive"))
      (node (ref "C9") (pin "1") (pinfunction "1_1") (pintype "passive"))
      (node (ref "CONN1") (pin "1") (pinfunction "1_1") (pintype "passive"))
      (node (ref "CONN2") (pin "3") (pinfunction "3_3") (pintype "passive"))
      (node (ref "CONN3") (pin "3") (pinfunction "3_3") (pintype "passive"))
      (node (ref "CONN3") (pin "4") (pinfunction "4_4") (pintype "passive"))
      (node (ref "J7") (pin "4") (pinfunction "4_4") (pintype "passive"))
      (node (ref "J7") (pin "5") (pinfunction "5_5") (pintype "passive"))
      (node (ref "J7") (pin "6") (pinfunction "6_6") (pintype "passive"))
      (node (ref "LED3") (pin "1") (pinfunction "1_1") (pintype "passive"))
      (node (ref "PS1") (pin "2") (pinfunction "GND_2") (pintype "passive"))
      (node (ref "R13") (pin "1") (pinfunction "CCW_1") (pintype "passive"))
      (node (ref "SW1") (pin "5") (pinfunction "5_5") (pintype "passive"))
      (node (ref "SW1") (pin "6") (pinfunction "6_6") (pintype "passive"))
      (node (ref "SW1") (pin "7") (pinfunction "7_7") (pintype "passive"))
      (node (ref "SW1") (pin "8") (pinfunction "8_8") (pintype "passive"))
      (node (ref "SW2") (pin "2") (pinfunction "2_2") (pintype "passive"))
      (node (ref "SW3") (pin "2") (pinfunction "2_2") (pintype "passive"))
      (node (ref "SW4") (pin "2") (pinfunction "2_2") (pintype "passive"))
      (node (ref "SW5") (pin "2") (pinfunction "2_2") (pintype "passive"))
      (node (ref "SW6") (pin "2") (pinfunction "2_2") (pintype "passive"))
      (node (ref "U1") (pin "29") (pinfunction "VSS_2_29") (pintype "passive"))
      (node (ref "U1") (pin "6") (pinfunction "VSS_1_6") (pintype "passive"))
      (node (ref "U2") (pin "1") (pinfunction "GND_1") (pintype "passive"))
      (node (ref "U3") (pin "4") (pinfunction "VSS_4") (pintype "passive"))
      (node (ref "U3") (pin "7") (pinfunction "PB0_7") (pintype "passive"))
      (node (ref "U4") (pin "4") (pinfunction "GND_4") (pintype "passive"))
    )
    (net (code "51") (name "Net-(LED3-Pad2)") (class "Default")
      (node (ref "LED3") (pin "2") (pinfunction "2_2") (pintype "passive"))
      (node (ref "R12") (pin "1") (pinfunction "1_1") (pintype "passive"))
    )
    (net (code "52") (name "Net-(PS1-Vin)") (class "Default")
      (node (ref "C4") (pin "2") (pinfunction "2_2") (pintype "passive"))
      (node (ref "C7") (pin "2") (pinfunction "2_2") (pintype "passive"))
      (node (ref "CONN3") (pin "1") (pinfunction "1_1") (pintype "passive"))
      (node (ref "CONN3") (pin "2") (pinfunction "2_2") (pintype "passive"))
      (node (ref "PS1") (pin "1") (pinfunction "Vin_1") (pintype "input"))
    )
    (net (code "53") (name "Net-(R13-WIPER)") (class "Default")
      (node (ref "R13") (pin "2") (pinfunction "WIPER_2") (pintype "passive"))
      (node (ref "U2") (pin "15") (pinfunction "R-EXT_15") (pintype "passive"))
      (node (ref "U3") (pin "6") (pinfunction "PW0_6") (pintype "passive"))
    )
    (net (code "54") (name "Net-(R20-Pad1)") (class "Default")
      (node (ref "R20") (pin "1") (pinfunction "1_1") (pintype "passive"))
      (node (ref "SW1") (pin "4") (pinfunction "4_4") (pintype "passive"))
    )
    (net (code "55") (name "Net-(R21-Pad1)") (class "Default")
      (node (ref "R21") (pin "1") (pinfunction "1_1") (pintype "passive"))
      (node (ref "SW1") (pin "3") (pinfunction "3_3") (pintype "passive"))
    )
    (net (code "56") (name "Net-(R22-Pad1)") (class "Default")
      (node (ref "R22") (pin "1") (pinfunction "1_1") (pintype "passive"))
      (node (ref "SW1") (pin "2") (pinfunction "2_2") (pintype "passive"))
    )
    (net (code "57") (name "Net-(R23-Pad1)") (class "Default")
      (node (ref "R23") (pin "1") (pinfunction "1_1") (pintype "passive"))
      (node (ref "SW1") (pin "1") (pinfunction "1_1") (pintype "passive"))
    )
    (net (code "58") (name "Net-(U2-~{OUT0})") (class "Default")
      (node (ref "R3") (pin "1") (pinfunction "1_1") (pintype "passive"))
      (node (ref "U2") (pin "5") (pinfunction "~{OUT0}_5") (pintype "passive"))
    )
    (net (code "59") (name "Net-(U2-~{OUT1})") (class "Default")
      (node (ref "R4") (pin "1") (pinfunction "1_1") (pintype "passive"))
      (node (ref "U2") (pin "6") (pinfunction "~{OUT1}_6") (pintype "passive"))
    )
    (net (code "60") (name "Net-(U2-~{OUT2})") (class "Default")
      (node (ref "R5") (pin "1") (pinfunction "1_1") (pintype "passive"))
      (node (ref "U2") (pin "7") (pinfunction "~{OUT2}_7") (pintype "passive"))
    )
    (net (code "61") (name "Net-(U2-~{OUT3})") (class "Default")
      (node (ref "R6") (pin "1") (pinfunction "1_1") (pintype "passive"))
      (node (ref "U2") (pin "8") (pinfunction "~{OUT3}_8") (pintype "passive"))
    )
    (net (code "62") (name "Net-(U2-~{OUT4})") (class "Default")
      (node (ref "R7") (pin "1") (pinfunction "1_1") (pintype "passive"))
      (node (ref "U2") (pin "9") (pinfunction "~{OUT4}_9") (pintype "passive"))
    )
    (net (code "63") (name "Net-(U2-~{OUT5})") (class "Default")
      (node (ref "R9") (pin "1") (pinfunction "1_1") (pintype "passive"))
      (node (ref "U2") (pin "10") (pinfunction "~{OUT5}_10") (pintype "passive"))
    )
    (net (code "64") (name "Net-(U2-~{OUT6})") (class "Default")
      (node (ref "R10") (pin "1") (pinfunction "1_1") (pintype "passive"))
      (node (ref "U2") (pin "11") (pinfunction "~{OUT6}_11") (pintype "passive"))
    )
    (net (code "65") (name "Net-(U2-~{OUT7})") (class "Default")
      (node (ref "R11") (pin "1") (pinfunction "1_1") (pintype "passive"))
      (node (ref "U2") (pin "12") (pinfunction "~{OUT7}_12") (pintype "passive"))
    )
    (net (code "66") (name "Net-(U4-VBAT)") (class "Default")
      (node (ref "BATT1") (pin "+") (pinfunction "+_+") (pintype "passive"))
      (node (ref "U4") (pin "3") (pinfunction "VBAT_3") (pintype "passive"))
    )
    (net (code "67") (name "Net-(U4-X1)") (class "Default")
      (node (ref "U4") (pin "1") (pinfunction "X1_1") (pintype "passive"))
      (node (ref "XTAL1") (pin "2") (pinfunction "2_2") (pintype "passive"))
    )
    (net (code "68") (name "Net-(U4-X2)") (class "Default")
      (node (ref "U4") (pin "2") (pinfunction "X2_2") (pintype "passive"))
      (node (ref "XTAL1") (pin "1") (pinfunction "1_1") (pintype "passive"))
    )
    (net (code "69") (name "unconnected-(LED1-ANODE_1-Pad14)") (class "Default")
      (node (ref "LED1") (pin "14") (pinfunction "ANODE_1_14") (pintype "passive"))
    )
    (net (code "70") (name "unconnected-(LED1-ANODE_2-Pad11)") (class "Default")
      (node (ref "LED1") (pin "11") (pinfunction "ANODE_2_11") (pintype "passive"))
    )
    (net (code "71") (name "unconnected-(LED1-ANODE_3-Pad10)") (class "Default")
      (node (ref "LED1") (pin "10") (pinfunction "ANODE_3_10") (pintype "passive"))
    )
    (net (code "72") (name "unconnected-(LED1-ANODE_4-Pad6)") (class "Default")
      (node (ref "LED1") (pin "6") (pinfunction "ANODE_4_6") (pintype "passive"))
    )
    (net (code "73") (name "unconnected-(LED1-ANODE_COLON-Pad7)") (class "Default")
      (node (ref "LED1") (pin "7") (pinfunction "ANODE_COLON_7") (pintype "passive"))
    )
    (net (code "74") (name "unconnected-(LED1-CATHODE_A-Pad13)") (class "Default")
      (node (ref "LED1") (pin "13") (pinfunction "CATHODE_A_13") (pintype "passive"))
    )
    (net (code "75") (name "unconnected-(LED1-CATHODE_B-Pad9)") (class "Default")
      (node (ref "LED1") (pin "9") (pinfunction "CATHODE_B_9") (pintype "passive"))
    )
    (net (code "76") (name "unconnected-(LED1-CATHODE_C-Pad4)") (class "Default")
      (node (ref "LED1") (pin "4") (pinfunction "CATHODE_C_4") (pintype "passive"))
    )
    (net (code "77") (name "unconnected-(LED1-CATHODE_COLON-Pad8)") (class "Default")
      (node (ref "LED1") (pin "8") (pinfunction "CATHODE_COLON_8") (pintype "passive"))
    )
    (net (code "78") (name "unconnected-(LED1-CATHODE_D-Pad2)") (class "Default")
      (node (ref "LED1") (pin "2") (pinfunction "CATHODE_D_2") (pintype "passive"))
    )
    (net (code "79") (name "unconnected-(LED1-CATHODE_DP-Pad3)") (class "Default")
      (node (ref "LED1") (pin "3") (pinfunction "CATHODE_DP_3") (pintype "passive"))
    )
    (net (code "80") (name "unconnected-(LED1-CATHODE_E-Pad1)") (class "Default")
      (node (ref "LED1") (pin "1") (pinfunction "CATHODE_E_1") (pintype "passive"))
    )
    (net (code "81") (name "unconnected-(LED1-CATHODE_F-Pad12)") (class "Default")
      (node (ref "LED1") (pin "12") (pinfunction "CATHODE_F_12") (pintype "passive"))
    )
    (net (code "82") (name "unconnected-(LED1-CATHODE_G-Pad5)") (class "Default")
      (node (ref "LED1") (pin "5") (pinfunction "CATHODE_G_5") (pintype "passive"))
    )
    (net (code "83") (name "unconnected-(LED2-ANODE_1-Pad1)") (class "Default")
      (node (ref "LED2") (pin "1") (pinfunction "ANODE_1_1") (pintype "passive"))
    )
    (net (code "84") (name "unconnected-(LED2-ANODE_2-Pad6)") (class "Default")
      (node (ref "LED2") (pin "6") (pinfunction "ANODE_2_6") (pintype "passive"))
    )
    (net (code "85") (name "unconnected-(LED2-CATHODE_A-Pad10)") (class "Default")
      (node (ref "LED2") (pin "10") (pinfunction "CATHODE_A_10") (pintype "passive"))
    )
    (net (code "86") (name "unconnected-(LED2-CATHODE_B-Pad9)") (class "Default")
      (node (ref "LED2") (pin "9") (pinfunction "CATHODE_B_9") (pintype "passive"))
    )
    (net (code "87") (name "unconnected-(LED2-CATHODE_C-Pad8)") (class "Default")
      (node (ref "LED2") (pin "8") (pinfunction "CATHODE_C_8") (pintype "passive"))
    )
    (net (code "88") (name "unconnected-(LED2-CATHODE_D-Pad5)") (class "Default")
      (node (ref "LED2") (pin "5") (pinfunction "CATHODE_D_5") (pintype "passive"))
    )
    (net (code "89") (name "unconnected-(LED2-CATHODE_DP-Pad7)") (class "Default")
      (node (ref "LED2") (pin "7") (pinfunction "CATHODE_DP_7") (pintype "passive"))
    )
    (net (code "90") (name "unconnected-(LED2-CATHODE_E-Pad4)") (class "Default")
      (node (ref "LED2") (pin "4") (pinfunction "CATHODE_E_4") (pintype "passive"))
    )
    (net (code "91") (name "unconnected-(LED2-CATHODE_F-Pad2)") (class "Default")
      (node (ref "LED2") (pin "2") (pinfunction "CATHODE_F_2") (pintype "passive"))
    )
    (net (code "92") (name "unconnected-(LED2-CATHODE_G-Pad3)") (class "Default")
      (node (ref "LED2") (pin "3") (pinfunction "CATHODE_G_3") (pintype "passive"))
    )
    (net (code "93") (name "unconnected-(LED4-ANODE_1-Pad1)") (class "Default")
      (node (ref "LED4") (pin "1") (pinfunction "ANODE_1_1") (pintype "passive"))
    )
    (net (code "94") (name "unconnected-(LED4-ANODE_2-Pad6)") (class "Default")
      (node (ref "LED4") (pin "6") (pinfunction "ANODE_2_6") (pintype "passive"))
    )
    (net (code "95") (name "unconnected-(LED4-CATHODE_A-Pad10)") (class "Default")
      (node (ref "LED4") (pin "10") (pinfunction "CATHODE_A_10") (pintype "passive"))
    )
    (net (code "96") (name "unconnected-(LED4-CATHODE_B-Pad9)") (class "Default")
      (node (ref "LED4") (pin "9") (pinfunction "CATHODE_B_9") (pintype "passive"))
    )
    (net (code "97") (name "unconnected-(LED4-CATHODE_C-Pad8)") (class "Default")
      (node (ref "LED4") (pin "8") (pinfunction "CATHODE_C_8") (pintype "passive"))
    )
    (net (code "98") (name "unconnected-(LED4-CATHODE_D-Pad5)") (class "Default")
      (node (ref "LED4") (pin "5") (pinfunction "CATHODE_D_5") (pintype "passive"))
    )
    (net (code "99") (name "unconnected-(LED4-CATHODE_DP-Pad7)") (class "Default")
      (node (ref "LED4") (pin "7") (pinfunction "CATHODE_DP_7") (pintype "passive"))
    )
    (net (code "100") (name "unconnected-(LED4-CATHODE_E-Pad4)") (class "Default")
      (node (ref "LED4") (pin "4") (pinfunction "CATHODE_E_4") (pintype "passive"))
    )
    (net (code "101") (name "unconnected-(LED4-CATHODE_F-Pad2)") (class "Default")
      (node (ref "LED4") (pin "2") (pinfunction "CATHODE_F_2") (pintype "passive"))
    )
    (net (code "102") (name "unconnected-(LED4-CATHODE_G-Pad3)") (class "Default")
      (node (ref "LED4") (pin "3") (pinfunction "CATHODE_G_3") (pintype "passive"))
    )
    (net (code "103") (name "unconnected-(R13-CW-Pad3)") (class "Default")
      (node (ref "R13") (pin "3") (pinfunction "CW_3") (pintype "passive"))
    )
    (net (code "104") (name "unconnected-(U1-NC_1-Pad12)") (class "Default")
      (node (ref "U1") (pin "12") (pinfunction "NC_1_12") (pintype "passive"))
    )
    (net (code "105") (name "unconnected-(U1-NC_2-Pad13)") (class "Default")
      (node (ref "U1") (pin "13") (pinfunction "NC_2_13") (pintype "passive"))
    )
    (net (code "106") (name "unconnected-(U1-NC_3-Pad33)") (class "Default")
      (node (ref "U1") (pin "33") (pinfunction "NC_3_33") (pintype "passive"))
    )
    (net (code "107") (name "unconnected-(U1-NC_4-Pad34)") (class "Default")
      (node (ref "U1") (pin "34") (pinfunction "NC_4_34") (pintype "passive"))
    )
    (net (code "108") (name "unconnected-(U1-RD6{slash}PSP6{slash}P1C-Pad4)") (class "Default")
      (node (ref "U1") (pin "4") (pinfunction "RD6/PSP6/P1C_4") (pintype "passive"))
    )
    (net (code "109") (name "unconnected-(U1-RD7{slash}PSP7{slash}P1D-Pad5)") (class "Default")
      (node (ref "U1") (pin "5") (pinfunction "RD7/PSP7/P1D_5") (pintype "passive"))
    )
    (net (code "110") (name "unconnected-(U1-RE0{slash}~{RD}{slash}AN5-Pad25)") (class "Default")
      (node (ref "U1") (pin "25") (pinfunction "RE0/~{RD}/AN5_25") (pintype "passive"))
    )
    (net (code "111") (name "unconnected-(U1-RE1{slash}~{WR}{slash}AN6-Pad26)") (class "Default")
      (node (ref "U1") (pin "26") (pinfunction "RE1/~{WR}/AN6_26") (pintype "passive"))
    )
    (net (code "112") (name "unconnected-(U1-RE2{slash}~{CS}{slash}AN7-Pad27)") (class "Default")
      (node (ref "U1") (pin "27") (pinfunction "RE2/~{CS}/AN7_27") (pintype "passive"))
    )
    (net (code "113") (name "unconnected-(U2-SDO-Pad14)") (class "Default")
      (node (ref "U2") (pin "14") (pinfunction "SDO_14") (pintype "passive"))
    )
    (net (code "114") (name "unconnected-(U3-PA0-Pad5)") (class "Default")
      (node (ref "U3") (pin "5") (pinfunction "PA0_5") (pintype "passive"))
    )
  )
)
